# SFP__Connectors.net
KiCad netlist of a schematic drawn in Altium Designer
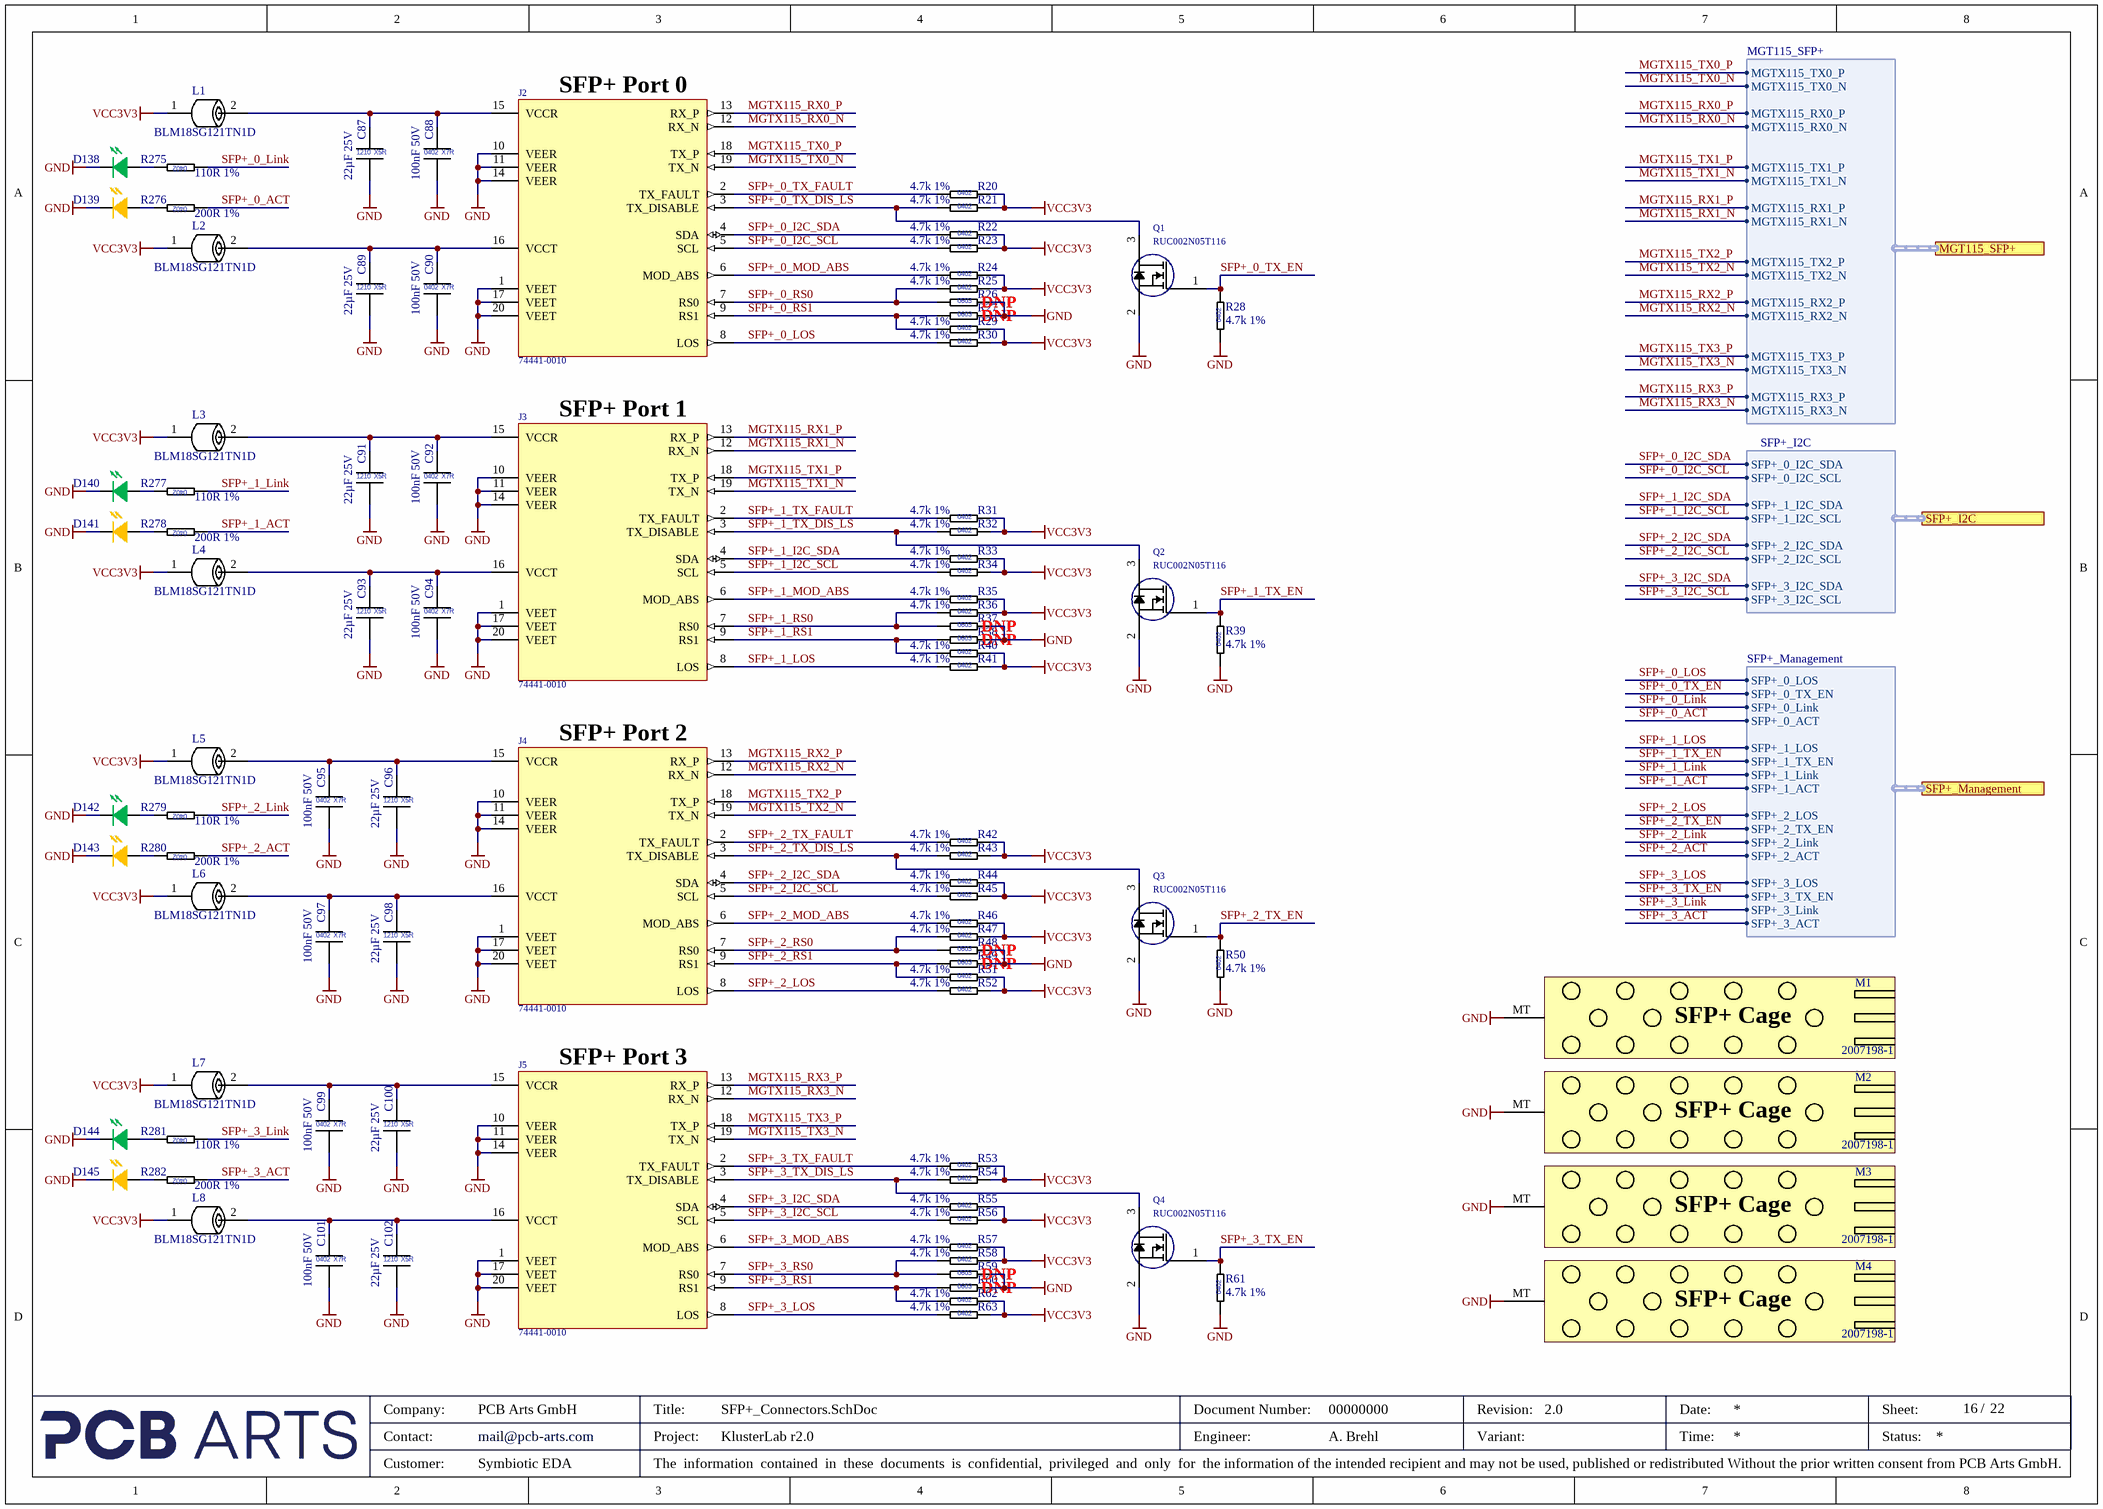
[diagram p0: SFP+_Connectors.SchDoc]

(export (version "E")
  (design (tool "Eeschema 10.0.6"))
  (components
    (comp (ref "C87")
      (value "22µF 25V")
      (footprint "Cap:CAP_1210")
      (description "Multilayer Ceramic Capacitors MLCC - SMD/SMT 1210 25VDC")
      (libsource (lib "Cap") (part "CAP_1210_22µF_25V"))
    )
    (comp (ref "C88")
      (value "100nF 50V")
      (footprint "Cap:CAP_0402_L")
      (description "Multilayer Ceramic Capacitors MLCC - SMD/SMT 0402 50VDC")
      (libsource (lib "Cap") (part "CAP_0402_100nF_50V"))
    )
    (comp (ref "C89")
      (value "22µF 25V")
      (footprint "Cap:CAP_1210")
      (description "Multilayer Ceramic Capacitors MLCC - SMD/SMT 1210 25VDC")
      (libsource (lib "Cap") (part "CAP_1210_22µF_25V"))
    )
    (comp (ref "C90")
      (value "100nF 50V")
      (footprint "Cap:CAP_0402_L")
      (description "Multilayer Ceramic Capacitors MLCC - SMD/SMT 0402 50VDC")
      (libsource (lib "Cap") (part "CAP_0402_100nF_50V"))
    )
    (comp (ref "C91")
      (value "22µF 25V")
      (footprint "Cap:CAP_1210")
      (description "Multilayer Ceramic Capacitors MLCC - SMD/SMT 1210 25VDC")
      (libsource (lib "Cap") (part "CAP_1210_22µF_25V"))
    )
    (comp (ref "C92")
      (value "100nF 50V")
      (footprint "Cap:CAP_0402_L")
      (description "Multilayer Ceramic Capacitors MLCC - SMD/SMT 0402 50VDC")
      (libsource (lib "Cap") (part "CAP_0402_100nF_50V"))
    )
    (comp (ref "C93")
      (value "22µF 25V")
      (footprint "Cap:CAP_1210")
      (description "Multilayer Ceramic Capacitors MLCC - SMD/SMT 1210 25VDC")
      (libsource (lib "Cap") (part "CAP_1210_22µF_25V"))
    )
    (comp (ref "C94")
      (value "100nF 50V")
      (footprint "Cap:CAP_0402_L")
      (description "Multilayer Ceramic Capacitors MLCC - SMD/SMT 0402 50VDC")
      (libsource (lib "Cap") (part "CAP_0402_100nF_50V"))
    )
    (comp (ref "C95")
      (value "100nF 50V")
      (footprint "Cap:CAP_0402_L")
      (description "Multilayer Ceramic Capacitors MLCC - SMD/SMT 0402 50VDC")
      (libsource (lib "Cap") (part "CAP_0402_100nF_50V"))
    )
    (comp (ref "C96")
      (value "22µF 25V")
      (footprint "Cap:CAP_1210")
      (description "Multilayer Ceramic Capacitors MLCC - SMD/SMT 1210 25VDC")
      (libsource (lib "Cap") (part "CAP_1210_22µF_25V"))
    )
    (comp (ref "C97")
      (value "100nF 50V")
      (footprint "Cap:CAP_0402_L")
      (description "Multilayer Ceramic Capacitors MLCC - SMD/SMT 0402 50VDC")
      (libsource (lib "Cap") (part "CAP_0402_100nF_50V"))
    )
    (comp (ref "C98")
      (value "22µF 25V")
      (footprint "Cap:CAP_1210")
      (description "Multilayer Ceramic Capacitors MLCC - SMD/SMT 1210 25VDC")
      (libsource (lib "Cap") (part "CAP_1210_22µF_25V"))
    )
    (comp (ref "C99")
      (value "100nF 50V")
      (footprint "Cap:CAP_0402_L")
      (description "Multilayer Ceramic Capacitors MLCC - SMD/SMT 0402 50VDC")
      (libsource (lib "Cap") (part "CAP_0402_100nF_50V"))
    )
    (comp (ref "C100")
      (value "22µF 25V")
      (footprint "Cap:CAP_1210")
      (description "Multilayer Ceramic Capacitors MLCC - SMD/SMT 1210 25VDC")
      (libsource (lib "Cap") (part "CAP_1210_22µF_25V"))
    )
    (comp (ref "C101")
      (value "100nF 50V")
      (footprint "Cap:CAP_0402_L")
      (description "Multilayer Ceramic Capacitors MLCC - SMD/SMT 0402 50VDC")
      (libsource (lib "Cap") (part "CAP_0402_100nF_50V"))
    )
    (comp (ref "C102")
      (value "22µF 25V")
      (footprint "Cap:CAP_1210")
      (description "Multilayer Ceramic Capacitors MLCC - SMD/SMT 1210 25VDC")
      (libsource (lib "Cap") (part "CAP_1210_22µF_25V"))
    )
    (comp (ref "D138")
      (value "LTST-S270KGKT")
      (footprint "Active:LED-0603 Sideview")
      (description "GREEN  0603 Light Emitting Diode")
      (libsource (lib "Active") (part "LED 0603 Green Sideview"))
    )
    (comp (ref "D139")
      (value "LTST-S270KFKT")
      (footprint "Active:LED-0603 Sideview")
      (description "ORANGE 0603 Light Emitting Diode")
      (libsource (lib "Active") (part "LED 0603 ORANGE Sideview"))
    )
    (comp (ref "D140")
      (value "LTST-S270KGKT")
      (footprint "Active:LED-0603 Sideview")
      (description "GREEN  0603 Light Emitting Diode")
      (libsource (lib "Active") (part "LED 0603 Green Sideview"))
    )
    (comp (ref "D141")
      (value "LTST-S270KFKT")
      (footprint "Active:LED-0603 Sideview")
      (description "ORANGE 0603 Light Emitting Diode")
      (libsource (lib "Active") (part "LED 0603 ORANGE Sideview"))
    )
    (comp (ref "D142")
      (value "LTST-S270KGKT")
      (footprint "Active:LED-0603 Sideview")
      (description "GREEN  0603 Light Emitting Diode")
      (libsource (lib "Active") (part "LED 0603 Green Sideview"))
    )
    (comp (ref "D143")
      (value "LTST-S270KFKT")
      (footprint "Active:LED-0603 Sideview")
      (description "ORANGE 0603 Light Emitting Diode")
      (libsource (lib "Active") (part "LED 0603 ORANGE Sideview"))
    )
    (comp (ref "D144")
      (value "LTST-S270KGKT")
      (footprint "Active:LED-0603 Sideview")
      (description "GREEN  0603 Light Emitting Diode")
      (libsource (lib "Active") (part "LED 0603 Green Sideview"))
    )
    (comp (ref "D145")
      (value "LTST-S270KFKT")
      (footprint "Active:LED-0603 Sideview")
      (description "ORANGE 0603 Light Emitting Diode")
      (libsource (lib "Active") (part "LED 0603 ORANGE Sideview"))
    )
    (comp (ref "J2")
      (value "74441-0010")
      (footprint "Conn:74441-0010")
      (description "20 Pin Right Angle 0.8mm SMD Card Edge Connector for SFP+")
      (libsource (lib "Conn") (part "74441-0010_Card Edge Connector for SFP+"))
    )
    (comp (ref "J3")
      (value "74441-0010")
      (footprint "Conn:74441-0010")
      (description "20 Pin Right Angle 0.8mm SMD Card Edge Connector for SFP+")
      (libsource (lib "Conn") (part "74441-0010_Card Edge Connector for SFP+"))
    )
    (comp (ref "J4")
      (value "74441-0010")
      (footprint "Conn:74441-0010")
      (description "20 Pin Right Angle 0.8mm SMD Card Edge Connector for SFP+")
      (libsource (lib "Conn") (part "74441-0010_Card Edge Connector for SFP+"))
    )
    (comp (ref "J5")
      (value "74441-0010")
      (footprint "Conn:74441-0010")
      (description "20 Pin Right Angle 0.8mm SMD Card Edge Connector for SFP+")
      (libsource (lib "Conn") (part "74441-0010_Card Edge Connector for SFP+"))
    )
    (comp (ref "L1")
      (value "BLM18SG121TN1D")
      (footprint "Indc:L_0603")
      (description "Ferritperlen BLM18_xN 0603 100MHz 120Ohm 3000mA 25mOhm RSER")
      (libsource (lib "Indc") (part "BLM18SG121TN1D_Ferrite Beads 0603 120Ohms 3000mA"))
    )
    (comp (ref "L2")
      (value "BLM18SG121TN1D")
      (footprint "Indc:L_0603")
      (description "Ferritperlen BLM18_xN 0603 100MHz 120Ohm 3000mA 25mOhm RSER")
      (libsource (lib "Indc") (part "BLM18SG121TN1D_Ferrite Beads 0603 120Ohms 3000mA"))
    )
    (comp (ref "L3")
      (value "BLM18SG121TN1D")
      (footprint "Indc:L_0603")
      (description "Ferritperlen BLM18_xN 0603 100MHz 120Ohm 3000mA 25mOhm RSER")
      (libsource (lib "Indc") (part "BLM18SG121TN1D_Ferrite Beads 0603 120Ohms 3000mA"))
    )
    (comp (ref "L4")
      (value "BLM18SG121TN1D")
      (footprint "Indc:L_0603")
      (description "Ferritperlen BLM18_xN 0603 100MHz 120Ohm 3000mA 25mOhm RSER")
      (libsource (lib "Indc") (part "BLM18SG121TN1D_Ferrite Beads 0603 120Ohms 3000mA"))
    )
    (comp (ref "L5")
      (value "BLM18SG121TN1D")
      (footprint "Indc:L_0603")
      (description "Ferritperlen BLM18_xN 0603 100MHz 120Ohm 3000mA 25mOhm RSER")
      (libsource (lib "Indc") (part "BLM18SG121TN1D_Ferrite Beads 0603 120Ohms 3000mA"))
    )
    (comp (ref "L6")
      (value "BLM18SG121TN1D")
      (footprint "Indc:L_0603")
      (description "Ferritperlen BLM18_xN 0603 100MHz 120Ohm 3000mA 25mOhm RSER")
      (libsource (lib "Indc") (part "BLM18SG121TN1D_Ferrite Beads 0603 120Ohms 3000mA"))
    )
    (comp (ref "L7")
      (value "BLM18SG121TN1D")
      (footprint "Indc:L_0603")
      (description "Ferritperlen BLM18_xN 0603 100MHz 120Ohm 3000mA 25mOhm RSER")
      (libsource (lib "Indc") (part "BLM18SG121TN1D_Ferrite Beads 0603 120Ohms 3000mA"))
    )
    (comp (ref "L8")
      (value "BLM18SG121TN1D")
      (footprint "Indc:L_0603")
      (description "Ferritperlen BLM18_xN 0603 100MHz 120Ohm 3000mA 25mOhm RSER")
      (libsource (lib "Indc") (part "BLM18SG121TN1D_Ferrite Beads 0603 120Ohms 3000mA"))
    )
    (comp (ref "M1")
      (value "2007198-1")
      (footprint "Conn:2007198-1")
      (description "2SFP+ Cage, 1x1, external EMV springs, no lightpipes")
      (libsource (lib "Conn") (part "2007198-1_2SFP+ Cage, 1x1, external EMV springs, no lightpipes"))
    )
    (comp (ref "M2")
      (value "2007198-1")
      (footprint "Conn:2007198-1")
      (description "2SFP+ Cage, 1x1, external EMV springs, no lightpipes")
      (libsource (lib "Conn") (part "2007198-1_2SFP+ Cage, 1x1, external EMV springs, no lightpipes"))
    )
    (comp (ref "M3")
      (value "2007198-1")
      (footprint "Conn:2007198-1")
      (description "2SFP+ Cage, 1x1, external EMV springs, no lightpipes")
      (libsource (lib "Conn") (part "2007198-1_2SFP+ Cage, 1x1, external EMV springs, no lightpipes"))
    )
    (comp (ref "M4")
      (value "2007198-1")
      (footprint "Conn:2007198-1")
      (description "2SFP+ Cage, 1x1, external EMV springs, no lightpipes")
      (libsource (lib "Conn") (part "2007198-1_2SFP+ Cage, 1x1, external EMV springs, no lightpipes"))
    )
    (comp (ref "Q1")
      (value "RUC002N05T116")
      (footprint "trans:SOT95P251X112-3N")
      (description "MOSFET N-Ch 1.2 VGS Spec")
      (libsource (lib "Trans") (part "RUC002N05T116_MOSFET N-Ch 1.2 VGS Spec"))
    )
    (comp (ref "Q2")
      (value "RUC002N05T116")
      (footprint "trans:SOT95P251X112-3N")
      (description "MOSFET N-Ch 1.2 VGS Spec")
      (libsource (lib "Trans") (part "RUC002N05T116_MOSFET N-Ch 1.2 VGS Spec"))
    )
    (comp (ref "Q3")
      (value "RUC002N05T116")
      (footprint "trans:SOT95P251X112-3N")
      (description "MOSFET N-Ch 1.2 VGS Spec")
      (libsource (lib "Trans") (part "RUC002N05T116_MOSFET N-Ch 1.2 VGS Spec"))
    )
    (comp (ref "Q4")
      (value "RUC002N05T116")
      (footprint "trans:SOT95P251X112-3N")
      (description "MOSFET N-Ch 1.2 VGS Spec")
      (libsource (lib "Trans") (part "RUC002N05T116_MOSFET N-Ch 1.2 VGS Spec"))
    )
    (comp (ref "R20")
      (value "4.7k 1%")
      (footprint "Res:RES_0402_L")
      (description "Thick Film Resistors - SMD 4.7kOhm 1%")
      (libsource (lib "Res") (part "RES_0402_4.7k_1%"))
    )
    (comp (ref "R21")
      (value "4.7k 1%")
      (footprint "Res:RES_0402_L")
      (description "Thick Film Resistors - SMD 4.7kOhm 1%")
      (libsource (lib "Res") (part "RES_0402_4.7k_1%"))
    )
    (comp (ref "R22")
      (value "4.7k 1%")
      (footprint "Res:RES_0402_L")
      (description "Thick Film Resistors - SMD 4.7kOhm 1%")
      (libsource (lib "Res") (part "RES_0402_4.7k_1%"))
    )
    (comp (ref "R23")
      (value "4.7k 1%")
      (footprint "Res:RES_0402_L")
      (description "Thick Film Resistors - SMD 4.7kOhm 1%")
      (libsource (lib "Res") (part "RES_0402_4.7k_1%"))
    )
    (comp (ref "R24")
      (value "4.7k 1%")
      (footprint "Res:RES_0402_L")
      (description "Thick Film Resistors - SMD 4.7kOhm 1%")
      (libsource (lib "Res") (part "RES_0402_4.7k_1%"))
    )
    (comp (ref "R25")
      (value "4.7k 1%")
      (footprint "Res:RES_0402_L")
      (description "Thick Film Resistors - SMD 4.7kOhm 1%")
      (libsource (lib "Res") (part "RES_0402_4.7k_1%"))
    )
    (comp (ref "R26")
      (value "0R Jumper")
      (footprint "Res:RES_0603_L")
      (description "Thick Film Resistors - SMD 0Ohm Jumper")
      (libsource (lib "Res") (part "RES_0603_0R_Jumper"))
    )
    (comp (ref "R27")
      (value "0R Jumper")
      (footprint "Res:RES_0603_L")
      (description "Thick Film Resistors - SMD 0Ohm Jumper")
      (libsource (lib "Res") (part "RES_0603_0R_Jumper"))
    )
    (comp (ref "R28")
      (value "4.7k 1%")
      (footprint "Res:RES_0402_L")
      (description "Thick Film Resistors - SMD 4.7kOhm 1%")
      (libsource (lib "Res") (part "RES_0402_4.7k_1%"))
    )
    (comp (ref "R29")
      (value "4.7k 1%")
      (footprint "Res:RES_0402_L")
      (description "Thick Film Resistors - SMD 4.7kOhm 1%")
      (libsource (lib "Res") (part "RES_0402_4.7k_1%"))
    )
    (comp (ref "R30")
      (value "4.7k 1%")
      (footprint "Res:RES_0402_L")
      (description "Thick Film Resistors - SMD 4.7kOhm 1%")
      (libsource (lib "Res") (part "RES_0402_4.7k_1%"))
    )
    (comp (ref "R31")
      (value "4.7k 1%")
      (footprint "Res:RES_0402_L")
      (description "Thick Film Resistors - SMD 4.7kOhm 1%")
      (libsource (lib "Res") (part "RES_0402_4.7k_1%"))
    )
    (comp (ref "R32")
      (value "4.7k 1%")
      (footprint "Res:RES_0402_L")
      (description "Thick Film Resistors - SMD 4.7kOhm 1%")
      (libsource (lib "Res") (part "RES_0402_4.7k_1%"))
    )
    (comp (ref "R33")
      (value "4.7k 1%")
      (footprint "Res:RES_0402_L")
      (description "Thick Film Resistors - SMD 4.7kOhm 1%")
      (libsource (lib "Res") (part "RES_0402_4.7k_1%"))
    )
    (comp (ref "R34")
      (value "4.7k 1%")
      (footprint "Res:RES_0402_L")
      (description "Thick Film Resistors - SMD 4.7kOhm 1%")
      (libsource (lib "Res") (part "RES_0402_4.7k_1%"))
    )
    (comp (ref "R35")
      (value "4.7k 1%")
      (footprint "Res:RES_0402_L")
      (description "Thick Film Resistors - SMD 4.7kOhm 1%")
      (libsource (lib "Res") (part "RES_0402_4.7k_1%"))
    )
    (comp (ref "R36")
      (value "4.7k 1%")
      (footprint "Res:RES_0402_L")
      (description "Thick Film Resistors - SMD 4.7kOhm 1%")
      (libsource (lib "Res") (part "RES_0402_4.7k_1%"))
    )
    (comp (ref "R37")
      (value "0R Jumper")
      (footprint "Res:RES_0603_L")
      (description "Thick Film Resistors - SMD 0Ohm Jumper")
      (libsource (lib "Res") (part "RES_0603_0R_Jumper"))
    )
    (comp (ref "R38")
      (value "0R Jumper")
      (footprint "Res:RES_0603_L")
      (description "Thick Film Resistors - SMD 0Ohm Jumper")
      (libsource (lib "Res") (part "RES_0603_0R_Jumper"))
    )
    (comp (ref "R39")
      (value "4.7k 1%")
      (footprint "Res:RES_0402_L")
      (description "Thick Film Resistors - SMD 4.7kOhm 1%")
      (libsource (lib "Res") (part "RES_0402_4.7k_1%"))
    )
    (comp (ref "R40")
      (value "4.7k 1%")
      (footprint "Res:RES_0402_L")
      (description "Thick Film Resistors - SMD 4.7kOhm 1%")
      (libsource (lib "Res") (part "RES_0402_4.7k_1%"))
    )
    (comp (ref "R41")
      (value "4.7k 1%")
      (footprint "Res:RES_0402_L")
      (description "Thick Film Resistors - SMD 4.7kOhm 1%")
      (libsource (lib "Res") (part "RES_0402_4.7k_1%"))
    )
    (comp (ref "R42")
      (value "4.7k 1%")
      (footprint "Res:RES_0402_L")
      (description "Thick Film Resistors - SMD 4.7kOhm 1%")
      (libsource (lib "Res") (part "RES_0402_4.7k_1%"))
    )
    (comp (ref "R43")
      (value "4.7k 1%")
      (footprint "Res:RES_0402_L")
      (description "Thick Film Resistors - SMD 4.7kOhm 1%")
      (libsource (lib "Res") (part "RES_0402_4.7k_1%"))
    )
    (comp (ref "R44")
      (value "4.7k 1%")
      (footprint "Res:RES_0402_L")
      (description "Thick Film Resistors - SMD 4.7kOhm 1%")
      (libsource (lib "Res") (part "RES_0402_4.7k_1%"))
    )
    (comp (ref "R45")
      (value "4.7k 1%")
      (footprint "Res:RES_0402_L")
      (description "Thick Film Resistors - SMD 4.7kOhm 1%")
      (libsource (lib "Res") (part "RES_0402_4.7k_1%"))
    )
    (comp (ref "R46")
      (value "4.7k 1%")
      (footprint "Res:RES_0402_L")
      (description "Thick Film Resistors - SMD 4.7kOhm 1%")
      (libsource (lib "Res") (part "RES_0402_4.7k_1%"))
    )
    (comp (ref "R47")
      (value "4.7k 1%")
      (footprint "Res:RES_0402_L")
      (description "Thick Film Resistors - SMD 4.7kOhm 1%")
      (libsource (lib "Res") (part "RES_0402_4.7k_1%"))
    )
    (comp (ref "R48")
      (value "0R Jumper")
      (footprint "Res:RES_0603_L")
      (description "Thick Film Resistors - SMD 0Ohm Jumper")
      (libsource (lib "Res") (part "RES_0603_0R_Jumper"))
    )
    (comp (ref "R49")
      (value "0R Jumper")
      (footprint "Res:RES_0603_L")
      (description "Thick Film Resistors - SMD 0Ohm Jumper")
      (libsource (lib "Res") (part "RES_0603_0R_Jumper"))
    )
    (comp (ref "R50")
      (value "4.7k 1%")
      (footprint "Res:RES_0402_L")
      (description "Thick Film Resistors - SMD 4.7kOhm 1%")
      (libsource (lib "Res") (part "RES_0402_4.7k_1%"))
    )
    (comp (ref "R51")
      (value "4.7k 1%")
      (footprint "Res:RES_0402_L")
      (description "Thick Film Resistors - SMD 4.7kOhm 1%")
      (libsource (lib "Res") (part "RES_0402_4.7k_1%"))
    )
    (comp (ref "R52")
      (value "4.7k 1%")
      (footprint "Res:RES_0402_L")
      (description "Thick Film Resistors - SMD 4.7kOhm 1%")
      (libsource (lib "Res") (part "RES_0402_4.7k_1%"))
    )
    (comp (ref "R53")
      (value "4.7k 1%")
      (footprint "Res:RES_0402_L")
      (description "Thick Film Resistors - SMD 4.7kOhm 1%")
      (libsource (lib "Res") (part "RES_0402_4.7k_1%"))
    )
    (comp (ref "R54")
      (value "4.7k 1%")
      (footprint "Res:RES_0402_L")
      (description "Thick Film Resistors - SMD 4.7kOhm 1%")
      (libsource (lib "Res") (part "RES_0402_4.7k_1%"))
    )
    (comp (ref "R55")
      (value "4.7k 1%")
      (footprint "Res:RES_0402_L")
      (description "Thick Film Resistors - SMD 4.7kOhm 1%")
      (libsource (lib "Res") (part "RES_0402_4.7k_1%"))
    )
    (comp (ref "R56")
      (value "4.7k 1%")
      (footprint "Res:RES_0402_L")
      (description "Thick Film Resistors - SMD 4.7kOhm 1%")
      (libsource (lib "Res") (part "RES_0402_4.7k_1%"))
    )
    (comp (ref "R57")
      (value "4.7k 1%")
      (footprint "Res:RES_0402_L")
      (description "Thick Film Resistors - SMD 4.7kOhm 1%")
      (libsource (lib "Res") (part "RES_0402_4.7k_1%"))
    )
    (comp (ref "R58")
      (value "4.7k 1%")
      (footprint "Res:RES_0402_L")
      (description "Thick Film Resistors - SMD 4.7kOhm 1%")
      (libsource (lib "Res") (part "RES_0402_4.7k_1%"))
    )
    (comp (ref "R59")
      (value "0R Jumper")
      (footprint "Res:RES_0603_L")
      (description "Thick Film Resistors - SMD 0Ohm Jumper")
      (libsource (lib "Res") (part "RES_0603_0R_Jumper"))
    )
    (comp (ref "R60")
      (value "0R Jumper")
      (footprint "Res:RES_0603_L")
      (description "Thick Film Resistors - SMD 0Ohm Jumper")
      (libsource (lib "Res") (part "RES_0603_0R_Jumper"))
    )
    (comp (ref "R61")
      (value "4.7k 1%")
      (footprint "Res:RES_0402_L")
      (description "Thick Film Resistors - SMD 4.7kOhm 1%")
      (libsource (lib "Res") (part "RES_0402_4.7k_1%"))
    )
    (comp (ref "R62")
      (value "4.7k 1%")
      (footprint "Res:RES_0402_L")
      (description "Thick Film Resistors - SMD 4.7kOhm 1%")
      (libsource (lib "Res") (part "RES_0402_4.7k_1%"))
    )
    (comp (ref "R63")
      (value "4.7k 1%")
      (footprint "Res:RES_0402_L")
      (description "Thick Film Resistors - SMD 4.7kOhm 1%")
      (libsource (lib "Res") (part "RES_0402_4.7k_1%"))
    )
    (comp (ref "R275")
      (value "110R 1%")
      (footprint "Res:RES_0402_L")
      (description "Thick Film Resistors - SMD 110Ohm 1%")
      (libsource (lib "Res") (part "RES_0402_110R_1%"))
    )
    (comp (ref "R276")
      (value "200R 1%")
      (footprint "Res:RES_0402_L")
      (description "Thick Film Resistors - SMD 200Ohm 1%")
      (libsource (lib "Res") (part "RES_0402_200R 1%"))
    )
    (comp (ref "R277")
      (value "110R 1%")
      (footprint "Res:RES_0402_L")
      (description "Thick Film Resistors - SMD 110Ohm 1%")
      (libsource (lib "Res") (part "RES_0402_110R_1%"))
    )
    (comp (ref "R278")
      (value "200R 1%")
      (footprint "Res:RES_0402_L")
      (description "Thick Film Resistors - SMD 200Ohm 1%")
      (libsource (lib "Res") (part "RES_0402_200R 1%"))
    )
    (comp (ref "R279")
      (value "110R 1%")
      (footprint "Res:RES_0402_L")
      (description "Thick Film Resistors - SMD 110Ohm 1%")
      (libsource (lib "Res") (part "RES_0402_110R_1%"))
    )
    (comp (ref "R280")
      (value "200R 1%")
      (footprint "Res:RES_0402_L")
      (description "Thick Film Resistors - SMD 200Ohm 1%")
      (libsource (lib "Res") (part "RES_0402_200R 1%"))
    )
    (comp (ref "R281")
      (value "110R 1%")
      (footprint "Res:RES_0402_L")
      (description "Thick Film Resistors - SMD 110Ohm 1%")
      (libsource (lib "Res") (part "RES_0402_110R_1%"))
    )
    (comp (ref "R282")
      (value "200R 1%")
      (footprint "Res:RES_0402_L")
      (description "Thick Film Resistors - SMD 200Ohm 1%")
      (libsource (lib "Res") (part "RES_0402_200R 1%"))
    )
  )
  (nets
    (net (code "4") (name "/MGTX115_RX0_N") (class "Default")
      (node (ref "J2") (pin "12") (pinfunction "RX_N_12") (pintype "output"))
    )
    (net (code "5") (name "/MGTX115_RX0_P") (class "Default")
      (node (ref "J2") (pin "13") (pinfunction "RX_P_13") (pintype "output"))
    )
    (net (code "6") (name "/MGTX115_RX1_N") (class "Default")
      (node (ref "J3") (pin "12") (pinfunction "RX_N_12") (pintype "output"))
    )
    (net (code "7") (name "/MGTX115_RX1_P") (class "Default")
      (node (ref "J3") (pin "13") (pinfunction "RX_P_13") (pintype "output"))
    )
    (net (code "8") (name "/MGTX115_RX2_N") (class "Default")
      (node (ref "J4") (pin "12") (pinfunction "RX_N_12") (pintype "output"))
    )
    (net (code "9") (name "/MGTX115_RX2_P") (class "Default")
      (node (ref "J4") (pin "13") (pinfunction "RX_P_13") (pintype "output"))
    )
    (net (code "10") (name "/MGTX115_RX3_N") (class "Default")
      (node (ref "J5") (pin "12") (pinfunction "RX_N_12") (pintype "output"))
    )
    (net (code "11") (name "/MGTX115_RX3_P") (class "Default")
      (node (ref "J5") (pin "13") (pinfunction "RX_P_13") (pintype "output"))
    )
    (net (code "12") (name "/MGTX115_TX0_N") (class "Default")
      (node (ref "J2") (pin "19") (pinfunction "TX_N_19") (pintype "input"))
    )
    (net (code "13") (name "/MGTX115_TX0_P") (class "Default")
      (node (ref "J2") (pin "18") (pinfunction "TX_P_18") (pintype "input"))
    )
    (net (code "14") (name "/MGTX115_TX1_N") (class "Default")
      (node (ref "J3") (pin "19") (pinfunction "TX_N_19") (pintype "input"))
    )
    (net (code "15") (name "/MGTX115_TX1_P") (class "Default")
      (node (ref "J3") (pin "18") (pinfunction "TX_P_18") (pintype "input"))
    )
    (net (code "16") (name "/MGTX115_TX2_N") (class "Default")
      (node (ref "J4") (pin "19") (pinfunction "TX_N_19") (pintype "input"))
    )
    (net (code "17") (name "/MGTX115_TX2_P") (class "Default")
      (node (ref "J4") (pin "18") (pinfunction "TX_P_18") (pintype "input"))
    )
    (net (code "18") (name "/MGTX115_TX3_N") (class "Default")
      (node (ref "J5") (pin "19") (pinfunction "TX_N_19") (pintype "input"))
    )
    (net (code "19") (name "/MGTX115_TX3_P") (class "Default")
      (node (ref "J5") (pin "18") (pinfunction "TX_P_18") (pintype "input"))
    )
    (net (code "20") (name "/SFP+_0_ACT") (class "Default")
      (node (ref "R276") (pin "1") (pinfunction "1_1") (pintype "passive"))
    )
    (net (code "21") (name "/SFP+_0_I2C_SCL") (class "Default")
      (node (ref "J2") (pin "5") (pinfunction "SCL_5") (pintype "input"))
      (node (ref "R23") (pin "1") (pinfunction "1_1") (pintype "passive"))
    )
    (net (code "22") (name "/SFP+_0_I2C_SDA") (class "Default")
      (node (ref "J2") (pin "4") (pinfunction "SDA_4") (pintype "bidirectional"))
      (node (ref "R22") (pin "1") (pinfunction "1_1") (pintype "passive"))
    )
    (net (code "23") (name "/SFP+_0_LOS") (class "Default")
      (node (ref "J2") (pin "8") (pinfunction "LOS_8") (pintype "output"))
      (node (ref "R30") (pin "1") (pinfunction "1_1") (pintype "passive"))
    )
    (net (code "24") (name "/SFP+_0_Link") (class "Default")
      (node (ref "R275") (pin "1") (pinfunction "1_1") (pintype "passive"))
    )
    (net (code "25") (name "/SFP+_0_MOD_ABS") (class "Default")
      (node (ref "J2") (pin "6") (pinfunction "MOD_ABS_6") (pintype "output"))
      (node (ref "R24") (pin "1") (pinfunction "1_1") (pintype "passive"))
    )
    (net (code "26") (name "/SFP+_0_RS0") (class "Default")
      (node (ref "J2") (pin "7") (pinfunction "RS0_7") (pintype "input"))
      (node (ref "R25") (pin "1") (pinfunction "1_1") (pintype "passive"))
      (node (ref "R26") (pin "1") (pinfunction "1_1") (pintype "passive"))
    )
    (net (code "27") (name "/SFP+_0_RS1") (class "Default")
      (node (ref "J2") (pin "9") (pinfunction "RS1_9") (pintype "input"))
      (node (ref "R27") (pin "1") (pinfunction "1_1") (pintype "passive"))
      (node (ref "R29") (pin "1") (pinfunction "1_1") (pintype "passive"))
    )
    (net (code "28") (name "/SFP+_0_TX_DIS_LS") (class "Default")
      (node (ref "J2") (pin "3") (pinfunction "TX_DISABLE_3") (pintype "input"))
      (node (ref "Q1") (pin "3") (pinfunction "S_3") (pintype "passive"))
      (node (ref "R21") (pin "1") (pinfunction "1_1") (pintype "passive"))
    )
    (net (code "29") (name "/SFP+_0_TX_EN") (class "Default")
      (node (ref "Q1") (pin "1") (pinfunction "G_1") (pintype "passive"))
      (node (ref "R28") (pin "2") (pinfunction "2_2") (pintype "passive"))
    )
    (net (code "30") (name "/SFP+_0_TX_FAULT") (class "Default")
      (node (ref "J2") (pin "2") (pinfunction "TX_FAULT_2") (pintype "output"))
      (node (ref "R20") (pin "1") (pinfunction "1_1") (pintype "passive"))
    )
    (net (code "31") (name "/SFP+_1_ACT") (class "Default")
      (node (ref "R278") (pin "1") (pinfunction "1_1") (pintype "passive"))
    )
    (net (code "32") (name "/SFP+_1_I2C_SCL") (class "Default")
      (node (ref "J3") (pin "5") (pinfunction "SCL_5") (pintype "input"))
      (node (ref "R34") (pin "1") (pinfunction "1_1") (pintype "passive"))
    )
    (net (code "33") (name "/SFP+_1_I2C_SDA") (class "Default")
      (node (ref "J3") (pin "4") (pinfunction "SDA_4") (pintype "bidirectional"))
      (node (ref "R33") (pin "1") (pinfunction "1_1") (pintype "passive"))
    )
    (net (code "34") (name "/SFP+_1_LOS") (class "Default")
      (node (ref "J3") (pin "8") (pinfunction "LOS_8") (pintype "output"))
      (node (ref "R41") (pin "1") (pinfunction "1_1") (pintype "passive"))
    )
    (net (code "35") (name "/SFP+_1_Link") (class "Default")
      (node (ref "R277") (pin "1") (pinfunction "1_1") (pintype "passive"))
    )
    (net (code "36") (name "/SFP+_1_MOD_ABS") (class "Default")
      (node (ref "J3") (pin "6") (pinfunction "MOD_ABS_6") (pintype "output"))
      (node (ref "R35") (pin "1") (pinfunction "1_1") (pintype "passive"))
    )
    (net (code "37") (name "/SFP+_1_RS0") (class "Default")
      (node (ref "J3") (pin "7") (pinfunction "RS0_7") (pintype "input"))
      (node (ref "R36") (pin "1") (pinfunction "1_1") (pintype "passive"))
      (node (ref "R37") (pin "1") (pinfunction "1_1") (pintype "passive"))
    )
    (net (code "38") (name "/SFP+_1_RS1") (class "Default")
      (node (ref "J3") (pin "9") (pinfunction "RS1_9") (pintype "input"))
      (node (ref "R38") (pin "1") (pinfunction "1_1") (pintype "passive"))
      (node (ref "R40") (pin "1") (pinfunction "1_1") (pintype "passive"))
    )
    (net (code "39") (name "/SFP+_1_TX_DIS_LS") (class "Default")
      (node (ref "J3") (pin "3") (pinfunction "TX_DISABLE_3") (pintype "input"))
      (node (ref "Q2") (pin "3") (pinfunction "S_3") (pintype "passive"))
      (node (ref "R32") (pin "1") (pinfunction "1_1") (pintype "passive"))
    )
    (net (code "40") (name "/SFP+_1_TX_EN") (class "Default")
      (node (ref "Q2") (pin "1") (pinfunction "G_1") (pintype "passive"))
      (node (ref "R39") (pin "2") (pinfunction "2_2") (pintype "passive"))
    )
    (net (code "41") (name "/SFP+_1_TX_FAULT") (class "Default")
      (node (ref "J3") (pin "2") (pinfunction "TX_FAULT_2") (pintype "output"))
      (node (ref "R31") (pin "1") (pinfunction "1_1") (pintype "passive"))
    )
    (net (code "42") (name "/SFP+_2_ACT") (class "Default")
      (node (ref "R280") (pin "1") (pinfunction "1_1") (pintype "passive"))
    )
    (net (code "43") (name "/SFP+_2_I2C_SCL") (class "Default")
      (node (ref "J4") (pin "5") (pinfunction "SCL_5") (pintype "input"))
      (node (ref "R45") (pin "1") (pinfunction "1_1") (pintype "passive"))
    )
    (net (code "44") (name "/SFP+_2_I2C_SDA") (class "Default")
      (node (ref "J4") (pin "4") (pinfunction "SDA_4") (pintype "bidirectional"))
      (node (ref "R44") (pin "1") (pinfunction "1_1") (pintype "passive"))
    )
    (net (code "45") (name "/SFP+_2_LOS") (class "Default")
      (node (ref "J4") (pin "8") (pinfunction "LOS_8") (pintype "output"))
      (node (ref "R52") (pin "1") (pinfunction "1_1") (pintype "passive"))
    )
    (net (code "46") (name "/SFP+_2_Link") (class "Default")
      (node (ref "R279") (pin "1") (pinfunction "1_1") (pintype "passive"))
    )
    (net (code "47") (name "/SFP+_2_MOD_ABS") (class "Default")
      (node (ref "J4") (pin "6") (pinfunction "MOD_ABS_6") (pintype "output"))
      (node (ref "R46") (pin "1") (pinfunction "1_1") (pintype "passive"))
    )
    (net (code "48") (name "/SFP+_2_RS0") (class "Default")
      (node (ref "J4") (pin "7") (pinfunction "RS0_7") (pintype "input"))
      (node (ref "R47") (pin "1") (pinfunction "1_1") (pintype "passive"))
      (node (ref "R48") (pin "1") (pinfunction "1_1") (pintype "passive"))
    )
    (net (code "49") (name "/SFP+_2_RS1") (class "Default")
      (node (ref "J4") (pin "9") (pinfunction "RS1_9") (pintype "input"))
      (node (ref "R49") (pin "1") (pinfunction "1_1") (pintype "passive"))
      (node (ref "R51") (pin "1") (pinfunction "1_1") (pintype "passive"))
    )
    (net (code "50") (name "/SFP+_2_TX_DIS_LS") (class "Default")
      (node (ref "J4") (pin "3") (pinfunction "TX_DISABLE_3") (pintype "input"))
      (node (ref "Q3") (pin "3") (pinfunction "S_3") (pintype "passive"))
      (node (ref "R43") (pin "1") (pinfunction "1_1") (pintype "passive"))
    )
    (net (code "51") (name "/SFP+_2_TX_EN") (class "Default")
      (node (ref "Q3") (pin "1") (pinfunction "G_1") (pintype "passive"))
      (node (ref "R50") (pin "2") (pinfunction "2_2") (pintype "passive"))
    )
    (net (code "52") (name "/SFP+_2_TX_FAULT") (class "Default")
      (node (ref "J4") (pin "2") (pinfunction "TX_FAULT_2") (pintype "output"))
      (node (ref "R42") (pin "1") (pinfunction "1_1") (pintype "passive"))
    )
    (net (code "53") (name "/SFP+_3_ACT") (class "Default")
      (node (ref "R282") (pin "1") (pinfunction "1_1") (pintype "passive"))
    )
    (net (code "54") (name "/SFP+_3_I2C_SCL") (class "Default")
      (node (ref "J5") (pin "5") (pinfunction "SCL_5") (pintype "input"))
      (node (ref "R56") (pin "1") (pinfunction "1_1") (pintype "passive"))
    )
    (net (code "55") (name "/SFP+_3_I2C_SDA") (class "Default")
      (node (ref "J5") (pin "4") (pinfunction "SDA_4") (pintype "bidirectional"))
      (node (ref "R55") (pin "1") (pinfunction "1_1") (pintype "passive"))
    )
    (net (code "56") (name "/SFP+_3_LOS") (class "Default")
      (node (ref "J5") (pin "8") (pinfunction "LOS_8") (pintype "output"))
      (node (ref "R63") (pin "1") (pinfunction "1_1") (pintype "passive"))
    )
    (net (code "57") (name "/SFP+_3_Link") (class "Default")
      (node (ref "R281") (pin "1") (pinfunction "1_1") (pintype "passive"))
    )
    (net (code "58") (name "/SFP+_3_MOD_ABS") (class "Default")
      (node (ref "J5") (pin "6") (pinfunction "MOD_ABS_6") (pintype "output"))
      (node (ref "R57") (pin "1") (pinfunction "1_1") (pintype "passive"))
    )
    (net (code "59") (name "/SFP+_3_RS0") (class "Default")
      (node (ref "J5") (pin "7") (pinfunction "RS0_7") (pintype "input"))
      (node (ref "R58") (pin "1") (pinfunction "1_1") (pintype "passive"))
      (node (ref "R59") (pin "1") (pinfunction "1_1") (pintype "passive"))
    )
    (net (code "60") (name "/SFP+_3_RS1") (class "Default")
      (node (ref "J5") (pin "9") (pinfunction "RS1_9") (pintype "input"))
      (node (ref "R60") (pin "1") (pinfunction "1_1") (pintype "passive"))
      (node (ref "R62") (pin "1") (pinfunction "1_1") (pintype "passive"))
    )
    (net (code "61") (name "/SFP+_3_TX_DIS_LS") (class "Default")
      (node (ref "J5") (pin "3") (pinfunction "TX_DISABLE_3") (pintype "input"))
      (node (ref "Q4") (pin "3") (pinfunction "S_3") (pintype "passive"))
      (node (ref "R54") (pin "1") (pinfunction "1_1") (pintype "passive"))
    )
    (net (code "62") (name "/SFP+_3_TX_EN") (class "Default")
      (node (ref "Q4") (pin "1") (pinfunction "G_1") (pintype "passive"))
      (node (ref "R61") (pin "2") (pinfunction "2_2") (pintype "passive"))
    )
    (net (code "63") (name "/SFP+_3_TX_FAULT") (class "Default")
      (node (ref "J5") (pin "2") (pinfunction "TX_FAULT_2") (pintype "output"))
      (node (ref "R53") (pin "1") (pinfunction "1_1") (pintype "passive"))
    )
    (net (code "67") (name "GND") (class "Default")
      (node (ref "C100") (pin "2") (pinfunction "2_2") (pintype "passive"))
      (node (ref "C101") (pin "2") (pinfunction "2_2") (pintype "passive"))
      (node (ref "C102") (pin "2") (pinfunction "2_2") (pintype "passive"))
      (node (ref "C87") (pin "2") (pinfunction "2_2") (pintype "passive"))
      (node (ref "C88") (pin "2") (pinfunction "2_2") (pintype "passive"))
      (node (ref "C89") (pin "2") (pinfunction "2_2") (pintype "passive"))
      (node (ref "C90") (pin "2") (pinfunction "2_2") (pintype "passive"))
      (node (ref "C91") (pin "2") (pinfunction "2_2") (pintype "passive"))
      (node (ref "C92") (pin "2") (pinfunction "2_2") (pintype "passive"))
      (node (ref "C93") (pin "2") (pinfunction "2_2") (pintype "passive"))
      (node (ref "C94") (pin "2") (pinfunction "2_2") (pintype "passive"))
      (node (ref "C95") (pin "2") (pinfunction "2_2") (pintype "passive"))
      (node (ref "C96") (pin "2") (pinfunction "2_2") (pintype "passive"))
      (node (ref "C97") (pin "2") (pinfunction "2_2") (pintype "passive"))
      (node (ref "C98") (pin "2") (pinfunction "2_2") (pintype "passive"))
      (node (ref "C99") (pin "2") (pinfunction "2_2") (pintype "passive"))
      (node (ref "D138") (pin "1") (pinfunction "1_1") (pintype "passive"))
      (node (ref "D139") (pin "1") (pinfunction "1_1") (pintype "passive"))
      (node (ref "D140") (pin "1") (pinfunction "1_1") (pintype "passive"))
      (node (ref "D141") (pin "1") (pinfunction "1_1") (pintype "passive"))
      (node (ref "D142") (pin "1") (pinfunction "1_1") (pintype "passive"))
      (node (ref "D143") (pin "1") (pinfunction "1_1") (pintype "passive"))
      (node (ref "D144") (pin "1") (pinfunction "1_1") (pintype "passive"))
      (node (ref "D145") (pin "1") (pinfunction "1_1") (pintype "passive"))
      (node (ref "J2") (pin "1") (pinfunction "VEET_1") (pintype "power_in"))
      (node (ref "J2") (pin "10") (pinfunction "VEER_10") (pintype "power_in"))
      (node (ref "J2") (pin "11") (pinfunction "VEER_11") (pintype "power_in"))
      (node (ref "J2") (pin "14") (pinfunction "VEER_14") (pintype "power_in"))
      (node (ref "J2") (pin "17") (pinfunction "VEET_17") (pintype "power_in"))
      (node (ref "J2") (pin "20") (pinfunction "VEET_20") (pintype "power_in"))
      (node (ref "J3") (pin "1") (pinfunction "VEET_1") (pintype "power_in"))
      (node (ref "J3") (pin "10") (pinfunction "VEER_10") (pintype "power_in"))
      (node (ref "J3") (pin "11") (pinfunction "VEER_11") (pintype "power_in"))
      (node (ref "J3") (pin "14") (pinfunction "VEER_14") (pintype "power_in"))
      (node (ref "J3") (pin "17") (pinfunction "VEET_17") (pintype "power_in"))
      (node (ref "J3") (pin "20") (pinfunction "VEET_20") (pintype "power_in"))
      (node (ref "J4") (pin "1") (pinfunction "VEET_1") (pintype "power_in"))
      (node (ref "J4") (pin "10") (pinfunction "VEER_10") (pintype "power_in"))
      (node (ref "J4") (pin "11") (pinfunction "VEER_11") (pintype "power_in"))
      (node (ref "J4") (pin "14") (pinfunction "VEER_14") (pintype "power_in"))
      (node (ref "J4") (pin "17") (pinfunction "VEET_17") (pintype "power_in"))
      (node (ref "J4") (pin "20") (pinfunction "VEET_20") (pintype "power_in"))
      (node (ref "J5") (pin "1") (pinfunction "VEET_1") (pintype "power_in"))
      (node (ref "J5") (pin "10") (pinfunction "VEER_10") (pintype "power_in"))
      (node (ref "J5") (pin "11") (pinfunction "VEER_11") (pintype "power_in"))
      (node (ref "J5") (pin "14") (pinfunction "VEER_14") (pintype "power_in"))
      (node (ref "J5") (pin "17") (pinfunction "VEET_17") (pintype "power_in"))
      (node (ref "J5") (pin "20") (pinfunction "VEET_20") (pintype "power_in"))
      (node (ref "M1") (pin "MT") (pinfunction "MT_MT") (pintype "passive"))
      (node (ref "M2") (pin "MT") (pinfunction "MT_MT") (pintype "passive"))
      (node (ref "M3") (pin "MT") (pinfunction "MT_MT") (pintype "passive"))
      (node (ref "M4") (pin "MT") (pinfunction "MT_MT") (pintype "passive"))
      (node (ref "Q1") (pin "2") (pinfunction "D_2") (pintype "passive"))
      (node (ref "Q2") (pin "2") (pinfunction "D_2") (pintype "passive"))
      (node (ref "Q3") (pin "2") (pinfunction "D_2") (pintype "passive"))
      (node (ref "Q4") (pin "2") (pinfunction "D_2") (pintype "passive"))
      (node (ref "R26") (pin "2") (pinfunction "2_2") (pintype "passive"))
      (node (ref "R27") (pin "2") (pinfunction "2_2") (pintype "passive"))
      (node (ref "R28") (pin "1") (pinfunction "1_1") (pintype "passive"))
      (node (ref "R37") (pin "2") (pinfunction "2_2") (pintype "passive"))
      (node (ref "R38") (pin "2") (pinfunction "2_2") (pintype "passive"))
      (node (ref "R39") (pin "1") (pinfunction "1_1") (pintype "passive"))
      (node (ref "R48") (pin "2") (pinfunction "2_2") (pintype "passive"))
      (node (ref "R49") (pin "2") (pinfunction "2_2") (pintype "passive"))
      (node (ref "R50") (pin "1") (pinfunction "1_1") (pintype "passive"))
      (node (ref "R59") (pin "2") (pinfunction "2_2") (pintype "passive"))
      (node (ref "R60") (pin "2") (pinfunction "2_2") (pintype "passive"))
      (node (ref "R61") (pin "1") (pinfunction "1_1") (pintype "passive"))
    )
    (net (code "68") (name "Net-(D138-Pad2)") (class "Default")
      (node (ref "D138") (pin "2") (pinfunction "2_2") (pintype "passive"))
      (node (ref "R275") (pin "2") (pinfunction "2_2") (pintype "passive"))
    )
    (net (code "69") (name "Net-(D139-Pad2)") (class "Default")
      (node (ref "D139") (pin "2") (pinfunction "2_2") (pintype "passive"))
      (node (ref "R276") (pin "2") (pinfunction "2_2") (pintype "passive"))
    )
    (net (code "70") (name "Net-(D140-Pad2)") (class "Default")
      (node (ref "D140") (pin "2") (pinfunction "2_2") (pintype "passive"))
      (node (ref "R277") (pin "2") (pinfunction "2_2") (pintype "passive"))
    )
    (net (code "71") (name "Net-(D141-Pad2)") (class "Default")
      (node (ref "D141") (pin "2") (pinfunction "2_2") (pintype "passive"))
      (node (ref "R278") (pin "2") (pinfunction "2_2") (pintype "passive"))
    )
    (net (code "72") (name "Net-(D142-Pad2)") (class "Default")
      (node (ref "D142") (pin "2") (pinfunction "2_2") (pintype "passive"))
      (node (ref "R279") (pin "2") (pinfunction "2_2") (pintype "passive"))
    )
    (net (code "73") (name "Net-(D143-Pad2)") (class "Default")
      (node (ref "D143") (pin "2") (pinfunction "2_2") (pintype "passive"))
      (node (ref "R280") (pin "2") (pinfunction "2_2") (pintype "passive"))
    )
    (net (code "74") (name "Net-(D144-Pad2)") (class "Default")
      (node (ref "D144") (pin "2") (pinfunction "2_2") (pintype "passive"))
      (node (ref "R281") (pin "2") (pinfunction "2_2") (pintype "passive"))
    )
    (net (code "75") (name "Net-(D145-Pad2)") (class "Default")
      (node (ref "D145") (pin "2") (pinfunction "2_2") (pintype "passive"))
      (node (ref "R282") (pin "2") (pinfunction "2_2") (pintype "passive"))
    )
    (net (code "76") (name "Net-(J2-VCCR)") (class "Default")
      (node (ref "C87") (pin "1") (pinfunction "1_1") (pintype "passive"))
      (node (ref "C88") (pin "1") (pinfunction "1_1") (pintype "passive"))
      (node (ref "J2") (pin "15") (pinfunction "VCCR_15") (pintype "power_in"))
      (node (ref "L1") (pin "2") (pinfunction "2_2") (pintype "passive"))
    )
    (net (code "77") (name "Net-(J2-VCCT)") (class "Default")
      (node (ref "C89") (pin "1") (pinfunction "1_1") (pintype "passive"))
      (node (ref "C90") (pin "1") (pinfunction "1_1") (pintype "passive"))
      (node (ref "J2") (pin "16") (pinfunction "VCCT_16") (pintype "power_in"))
      (node (ref "L2") (pin "2") (pinfunction "2_2") (pintype "passive"))
    )
    (net (code "78") (name "Net-(J3-VCCR)") (class "Default")
      (node (ref "C91") (pin "1") (pinfunction "1_1") (pintype "passive"))
      (node (ref "C92") (pin "1") (pinfunction "1_1") (pintype "passive"))
      (node (ref "J3") (pin "15") (pinfunction "VCCR_15") (pintype "power_in"))
      (node (ref "L3") (pin "2") (pinfunction "2_2") (pintype "passive"))
    )
    (net (code "79") (name "Net-(J3-VCCT)") (class "Default")
      (node (ref "C93") (pin "1") (pinfunction "1_1") (pintype "passive"))
      (node (ref "C94") (pin "1") (pinfunction "1_1") (pintype "passive"))
      (node (ref "J3") (pin "16") (pinfunction "VCCT_16") (pintype "power_in"))
      (node (ref "L4") (pin "2") (pinfunction "2_2") (pintype "passive"))
    )
    (net (code "80") (name "Net-(J4-VCCR)") (class "Default")
      (node (ref "C95") (pin "1") (pinfunction "1_1") (pintype "passive"))
      (node (ref "C96") (pin "1") (pinfunction "1_1") (pintype "passive"))
      (node (ref "J4") (pin "15") (pinfunction "VCCR_15") (pintype "power_in"))
      (node (ref "L5") (pin "2") (pinfunction "2_2") (pintype "passive"))
    )
    (net (code "81") (name "Net-(J4-VCCT)") (class "Default")
      (node (ref "C97") (pin "1") (pinfunction "1_1") (pintype "passive"))
      (node (ref "C98") (pin "1") (pinfunction "1_1") (pintype "passive"))
      (node (ref "J4") (pin "16") (pinfunction "VCCT_16") (pintype "power_in"))
      (node (ref "L6") (pin "2") (pinfunction "2_2") (pintype "passive"))
    )
    (net (code "82") (name "Net-(J5-VCCR)") (class "Default")
      (node (ref "C100") (pin "1") (pinfunction "1_1") (pintype "passive"))
      (node (ref "C99") (pin "1") (pinfunction "1_1") (pintype "passive"))
      (node (ref "J5") (pin "15") (pinfunction "VCCR_15") (pintype "power_in"))
      (node (ref "L7") (pin "2") (pinfunction "2_2") (pintype "passive"))
    )
    (net (code "83") (name "Net-(J5-VCCT)") (class "Default")
      (node (ref "C101") (pin "1") (pinfunction "1_1") (pintype "passive"))
      (node (ref "C102") (pin "1") (pinfunction "1_1") (pintype "passive"))
      (node (ref "J5") (pin "16") (pinfunction "VCCT_16") (pintype "power_in"))
      (node (ref "L8") (pin "2") (pinfunction "2_2") (pintype "passive"))
    )
    (net (code "84") (name "VCC3V3") (class "Default")
      (node (ref "L1") (pin "1") (pinfunction "1_1") (pintype "passive"))
      (node (ref "L2") (pin "1") (pinfunction "1_1") (pintype "passive"))
      (node (ref "L3") (pin "1") (pinfunction "1_1") (pintype "passive"))
      (node (ref "L4") (pin "1") (pinfunction "1_1") (pintype "passive"))
      (node (ref "L5") (pin "1") (pinfunction "1_1") (pintype "passive"))
      (node (ref "L6") (pin "1") (pinfunction "1_1") (pintype "passive"))
      (node (ref "L7") (pin "1") (pinfunction "1_1") (pintype "passive"))
      (node (ref "L8") (pin "1") (pinfunction "1_1") (pintype "passive"))
      (node (ref "R20") (pin "2") (pinfunction "2_2") (pintype "passive"))
      (node (ref "R21") (pin "2") (pinfunction "2_2") (pintype "passive"))
      (node (ref "R22") (pin "2") (pinfunction "2_2") (pintype "passive"))
      (node (ref "R23") (pin "2") (pinfunction "2_2") (pintype "passive"))
      (node (ref "R24") (pin "2") (pinfunction "2_2") (pintype "passive"))
      (node (ref "R25") (pin "2") (pinfunction "2_2") (pintype "passive"))
      (node (ref "R29") (pin "2") (pinfunction "2_2") (pintype "passive"))
      (node (ref "R30") (pin "2") (pinfunction "2_2") (pintype "passive"))
      (node (ref "R31") (pin "2") (pinfunction "2_2") (pintype "passive"))
      (node (ref "R32") (pin "2") (pinfunction "2_2") (pintype "passive"))
      (node (ref "R33") (pin "2") (pinfunction "2_2") (pintype "passive"))
      (node (ref "R34") (pin "2") (pinfunction "2_2") (pintype "passive"))
      (node (ref "R35") (pin "2") (pinfunction "2_2") (pintype "passive"))
      (node (ref "R36") (pin "2") (pinfunction "2_2") (pintype "passive"))
      (node (ref "R40") (pin "2") (pinfunction "2_2") (pintype "passive"))
      (node (ref "R41") (pin "2") (pinfunction "2_2") (pintype "passive"))
      (node (ref "R42") (pin "2") (pinfunction "2_2") (pintype "passive"))
      (node (ref "R43") (pin "2") (pinfunction "2_2") (pintype "passive"))
      (node (ref "R44") (pin "2") (pinfunction "2_2") (pintype "passive"))
      (node (ref "R45") (pin "2") (pinfunction "2_2") (pintype "passive"))
      (node (ref "R46") (pin "2") (pinfunction "2_2") (pintype "passive"))
      (node (ref "R47") (pin "2") (pinfunction "2_2") (pintype "passive"))
      (node (ref "R51") (pin "2") (pinfunction "2_2") (pintype "passive"))
      (node (ref "R52") (pin "2") (pinfunction "2_2") (pintype "passive"))
      (node (ref "R53") (pin "2") (pinfunction "2_2") (pintype "passive"))
      (node (ref "R54") (pin "2") (pinfunction "2_2") (pintype "passive"))
      (node (ref "R55") (pin "2") (pinfunction "2_2") (pintype "passive"))
      (node (ref "R56") (pin "2") (pinfunction "2_2") (pintype "passive"))
      (node (ref "R57") (pin "2") (pinfunction "2_2") (pintype "passive"))
      (node (ref "R58") (pin "2") (pinfunction "2_2") (pintype "passive"))
      (node (ref "R62") (pin "2") (pinfunction "2_2") (pintype "passive"))
      (node (ref "R63") (pin "2") (pinfunction "2_2") (pintype "passive"))
    )
  )
)
